# Controller_Board_Interface.net
KiCad netlist of a schematic drawn in Altium Designer
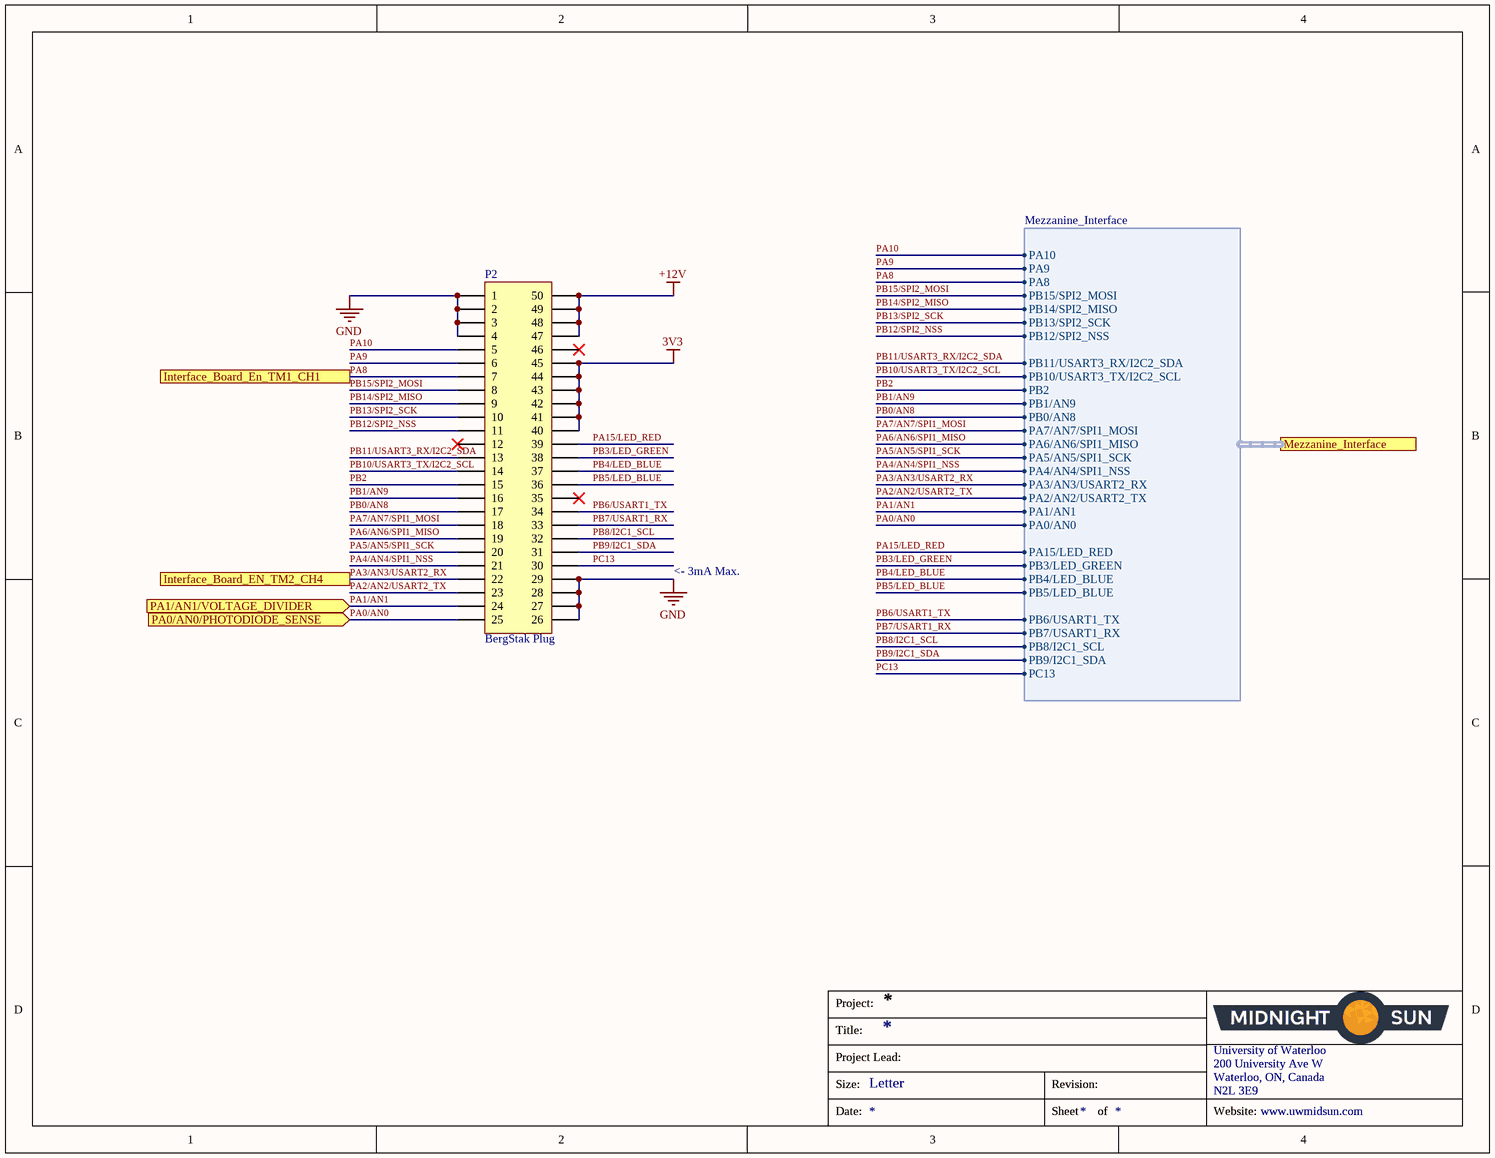
[diagram p0: Controller Board Interface.SchDoc]

(export (version "E")
  (design (tool "Eeschema 10.0.6"))
  (components
    (comp (ref "P2")
      (value "CONN 50POS Bergstak Plug 0.02\"")
      (footprint "CONN, Bergstak 50 Pos Plug")
      (description "50 Position Connector Plug, Outer Shroud Contacts Surface Mount Gold")
      (fields (field (name "SERIES") "BergStak Plug"))
      (libsource (lib "Schematic Diagrams") (part "CONN 50POS Bergstak Plug 0.02{dblquote}"))
    )
  )
  (nets
    (net (code "2") (name "+12V") (class "Default")
      (node (ref "P2") (pin "47") (pinfunction "47_47") (pintype "passive"))
      (node (ref "P2") (pin "48") (pinfunction "48_48") (pintype "passive"))
      (node (ref "P2") (pin "49") (pinfunction "49_49") (pintype "passive"))
      (node (ref "P2") (pin "50") (pinfunction "50_50") (pintype "passive"))
    )
    (net (code "3") (name "/PA0{slash}AN0") (class "Default")
      (node (ref "P2") (pin "25") (pinfunction "25_25") (pintype "passive"))
    )
    (net (code "4") (name "/PA1{slash}AN1") (class "Default")
      (node (ref "P2") (pin "24") (pinfunction "24_24") (pintype "passive"))
    )
    (net (code "5") (name "/PA2{slash}AN2{slash}USART2_TX") (class "Default")
      (node (ref "P2") (pin "23") (pinfunction "23_23") (pintype "passive"))
    )
    (net (code "6") (name "/PA3{slash}AN3{slash}USART2_RX") (class "Default")
      (node (ref "P2") (pin "22") (pinfunction "22_22") (pintype "passive"))
    )
    (net (code "7") (name "/PA4{slash}AN4{slash}SPI1_NSS") (class "Default")
      (node (ref "P2") (pin "21") (pinfunction "21_21") (pintype "passive"))
    )
    (net (code "8") (name "/PA5{slash}AN5{slash}SPI1_SCK") (class "Default")
      (node (ref "P2") (pin "20") (pinfunction "20_20") (pintype "passive"))
    )
    (net (code "9") (name "/PA6{slash}AN6{slash}SPI1_MISO") (class "Default")
      (node (ref "P2") (pin "19") (pinfunction "19_19") (pintype "passive"))
    )
    (net (code "10") (name "/PA7{slash}AN7{slash}SPI1_MOSI") (class "Default")
      (node (ref "P2") (pin "18") (pinfunction "18_18") (pintype "passive"))
    )
    (net (code "11") (name "/PA8") (class "Default")
      (node (ref "P2") (pin "7") (pinfunction "7_7") (pintype "passive"))
    )
    (net (code "12") (name "/PA9") (class "Default")
      (node (ref "P2") (pin "6") (pinfunction "6_6") (pintype "passive"))
    )
    (net (code "13") (name "/PA10") (class "Default")
      (node (ref "P2") (pin "5") (pinfunction "5_5") (pintype "passive"))
    )
    (net (code "14") (name "/PA15{slash}LED_RED") (class "Default")
      (node (ref "P2") (pin "39") (pinfunction "39_39") (pintype "passive"))
    )
    (net (code "15") (name "/PB0{slash}AN8") (class "Default")
      (node (ref "P2") (pin "17") (pinfunction "17_17") (pintype "passive"))
    )
    (net (code "16") (name "/PB1{slash}AN9") (class "Default")
      (node (ref "P2") (pin "16") (pinfunction "16_16") (pintype "passive"))
    )
    (net (code "17") (name "/PB2") (class "Default")
      (node (ref "P2") (pin "15") (pinfunction "15_15") (pintype "passive"))
    )
    (net (code "18") (name "/PB3{slash}LED_GREEN") (class "Default")
      (node (ref "P2") (pin "38") (pinfunction "38_38") (pintype "passive"))
    )
    (net (code "19") (name "/PB4{slash}LED_BLUE") (class "Default")
      (node (ref "P2") (pin "37") (pinfunction "37_37") (pintype "passive"))
    )
    (net (code "20") (name "/PB5{slash}LED_BLUE") (class "Default")
      (node (ref "P2") (pin "36") (pinfunction "36_36") (pintype "passive"))
    )
    (net (code "21") (name "/PB6{slash}USART1_TX") (class "Default")
      (node (ref "P2") (pin "34") (pinfunction "34_34") (pintype "passive"))
    )
    (net (code "22") (name "/PB7{slash}USART1_RX") (class "Default")
      (node (ref "P2") (pin "33") (pinfunction "33_33") (pintype "passive"))
    )
    (net (code "23") (name "/PB8{slash}I2C1_SCL") (class "Default")
      (node (ref "P2") (pin "32") (pinfunction "32_32") (pintype "passive"))
    )
    (net (code "24") (name "/PB9{slash}I2C1_SDA") (class "Default")
      (node (ref "P2") (pin "31") (pinfunction "31_31") (pintype "passive"))
    )
    (net (code "25") (name "/PB10{slash}USART3_TX{slash}I2C2_SCL") (class "Default")
      (node (ref "P2") (pin "14") (pinfunction "14_14") (pintype "passive"))
    )
    (net (code "26") (name "/PB11{slash}USART3_RX{slash}I2C2_SDA") (class "Default")
      (node (ref "P2") (pin "13") (pinfunction "13_13") (pintype "passive"))
    )
    (net (code "27") (name "/PB12{slash}SPI2_NSS") (class "Default")
      (node (ref "P2") (pin "11") (pinfunction "11_11") (pintype "passive"))
    )
    (net (code "28") (name "/PB13{slash}SPI2_SCK") (class "Default")
      (node (ref "P2") (pin "10") (pinfunction "10_10") (pintype "passive"))
    )
    (net (code "29") (name "/PB14{slash}SPI2_MISO") (class "Default")
      (node (ref "P2") (pin "9") (pinfunction "9_9") (pintype "passive"))
    )
    (net (code "30") (name "/PB15{slash}SPI2_MOSI") (class "Default")
      (node (ref "P2") (pin "8") (pinfunction "8_8") (pintype "passive"))
    )
    (net (code "31") (name "/PC13") (class "Default")
      (node (ref "P2") (pin "30") (pinfunction "30_30") (pintype "passive"))
    )
    (net (code "33") (name "3V3") (class "Default")
      (node (ref "P2") (pin "40") (pinfunction "40_40") (pintype "passive"))
      (node (ref "P2") (pin "41") (pinfunction "41_41") (pintype "passive"))
      (node (ref "P2") (pin "42") (pinfunction "42_42") (pintype "passive"))
      (node (ref "P2") (pin "43") (pinfunction "43_43") (pintype "passive"))
      (node (ref "P2") (pin "44") (pinfunction "44_44") (pintype "passive"))
      (node (ref "P2") (pin "45") (pinfunction "45_45") (pintype "passive"))
    )
    (net (code "34") (name "GND") (class "Default")
      (node (ref "P2") (pin "1") (pinfunction "1_1") (pintype "passive"))
      (node (ref "P2") (pin "2") (pinfunction "2_2") (pintype "passive"))
      (node (ref "P2") (pin "26") (pinfunction "26_26") (pintype "passive"))
      (node (ref "P2") (pin "27") (pinfunction "27_27") (pintype "passive"))
      (node (ref "P2") (pin "28") (pinfunction "28_28") (pintype "passive"))
      (node (ref "P2") (pin "29") (pinfunction "29_29") (pintype "passive"))
      (node (ref "P2") (pin "3") (pinfunction "3_3") (pintype "passive"))
      (node (ref "P2") (pin "4") (pinfunction "4_4") (pintype "passive"))
    )
    (net (code "35") (name "unconnected-(P2-Pad12)") (class "Default")
      (node (ref "P2") (pin "12") (pinfunction "12_12") (pintype "passive+no_connect"))
    )
    (net (code "36") (name "unconnected-(P2-Pad35)") (class "Default")
      (node (ref "P2") (pin "35") (pinfunction "35_35") (pintype "passive+no_connect"))
    )
    (net (code "37") (name "unconnected-(P2-Pad46)") (class "Default")
      (node (ref "P2") (pin "46") (pinfunction "46_46") (pintype "passive+no_connect"))
    )
  )
)
